# TestPoints.net
KiCad netlist of a schematic drawn in Altium Designer
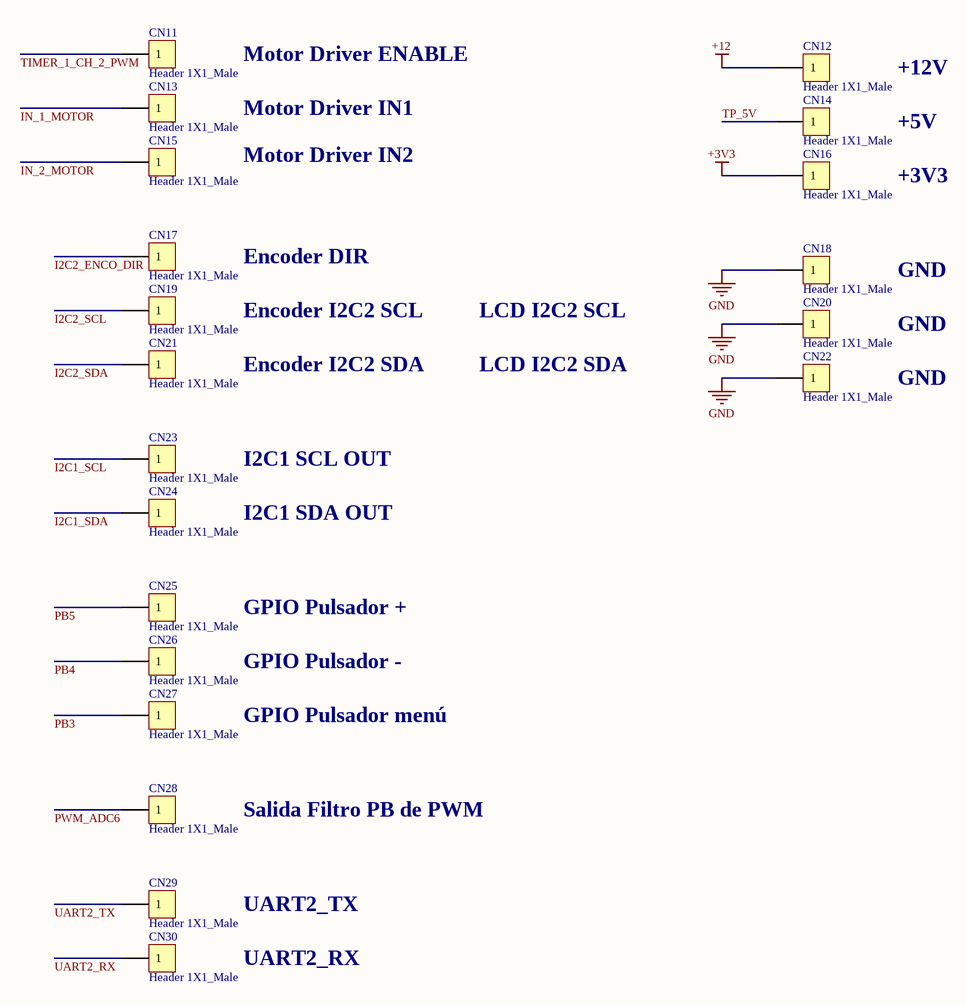
[diagram p0: TestPoints.SchDoc]

(export (version "E")
  (design (tool "Eeschema 10.0.6"))
  (components
    (comp (ref "CN11")
      (value "Header 1X1_Male")
      (footprint "1*1P_MALE")
      (description "Header, 1-Pin, Single row,male")
      (fields (field (name "PUBLISHER") "Altium Limited"))
      (libsource (lib "ProyectoTD3") (part "Header 1X1_Male"))
    )
    (comp (ref "CN12")
      (value "Header 1X1_Male")
      (footprint "1*1P_MALE")
      (description "Header, 1-Pin, Single row,male")
      (fields (field (name "PUBLISHER") "Altium Limited"))
      (libsource (lib "ProyectoTD3") (part "Header 1X1_Male"))
    )
    (comp (ref "CN13")
      (value "Header 1X1_Male")
      (footprint "1*1P_MALE")
      (description "Header, 1-Pin, Single row,male")
      (fields (field (name "PUBLISHER") "Altium Limited"))
      (libsource (lib "ProyectoTD3") (part "Header 1X1_Male"))
    )
    (comp (ref "CN14")
      (value "Header 1X1_Male")
      (footprint "1*1P_MALE")
      (description "Header, 1-Pin, Single row,male")
      (fields (field (name "PUBLISHER") "Altium Limited"))
      (libsource (lib "ProyectoTD3") (part "Header 1X1_Male"))
    )
    (comp (ref "CN15")
      (value "Header 1X1_Male")
      (footprint "1*1P_MALE")
      (description "Header, 1-Pin, Single row,male")
      (fields (field (name "PUBLISHER") "Altium Limited"))
      (libsource (lib "ProyectoTD3") (part "Header 1X1_Male"))
    )
    (comp (ref "CN16")
      (value "Header 1X1_Male")
      (footprint "1*1P_MALE")
      (description "Header, 1-Pin, Single row,male")
      (fields (field (name "PUBLISHER") "Altium Limited"))
      (libsource (lib "ProyectoTD3") (part "Header 1X1_Male"))
    )
    (comp (ref "CN17")
      (value "Header 1X1_Male")
      (footprint "1*1P_MALE")
      (description "Header, 1-Pin, Single row,male")
      (fields (field (name "PUBLISHER") "Altium Limited"))
      (libsource (lib "ProyectoTD3") (part "Header 1X1_Male"))
    )
    (comp (ref "CN18")
      (value "Header 1X1_Male")
      (footprint "1*1P_MALE")
      (description "Header, 1-Pin, Single row,male")
      (fields (field (name "PUBLISHER") "Altium Limited"))
      (libsource (lib "ProyectoTD3") (part "Header 1X1_Male"))
    )
    (comp (ref "CN19")
      (value "Header 1X1_Male")
      (footprint "1*1P_MALE")
      (description "Header, 1-Pin, Single row,male")
      (fields (field (name "PUBLISHER") "Altium Limited"))
      (libsource (lib "ProyectoTD3") (part "Header 1X1_Male"))
    )
    (comp (ref "CN20")
      (value "Header 1X1_Male")
      (footprint "1*1P_MALE")
      (description "Header, 1-Pin, Single row,male")
      (fields (field (name "PUBLISHER") "Altium Limited"))
      (libsource (lib "ProyectoTD3") (part "Header 1X1_Male"))
    )
    (comp (ref "CN21")
      (value "Header 1X1_Male")
      (footprint "1*1P_MALE")
      (description "Header, 1-Pin, Single row,male")
      (fields (field (name "PUBLISHER") "Altium Limited"))
      (libsource (lib "ProyectoTD3") (part "Header 1X1_Male"))
    )
    (comp (ref "CN22")
      (value "Header 1X1_Male")
      (footprint "1*1P_MALE")
      (description "Header, 1-Pin, Single row,male")
      (fields (field (name "PUBLISHER") "Altium Limited"))
      (libsource (lib "ProyectoTD3") (part "Header 1X1_Male"))
    )
    (comp (ref "CN23")
      (value "Header 1X1_Male")
      (footprint "1*1P_MALE")
      (description "Header, 1-Pin, Single row,male")
      (fields (field (name "PUBLISHER") "Altium Limited"))
      (libsource (lib "ProyectoTD3") (part "Header 1X1_Male"))
    )
    (comp (ref "CN24")
      (value "Header 1X1_Male")
      (footprint "1*1P_MALE")
      (description "Header, 1-Pin, Single row,male")
      (fields (field (name "PUBLISHER") "Altium Limited"))
      (libsource (lib "ProyectoTD3") (part "Header 1X1_Male"))
    )
    (comp (ref "CN25")
      (value "Header 1X1_Male")
      (footprint "1*1P_MALE")
      (description "Header, 1-Pin, Single row,male")
      (fields (field (name "PUBLISHER") "Altium Limited"))
      (libsource (lib "ProyectoTD3") (part "Header 1X1_Male"))
    )
    (comp (ref "CN26")
      (value "Header 1X1_Male")
      (footprint "1*1P_MALE")
      (description "Header, 1-Pin, Single row,male")
      (fields (field (name "PUBLISHER") "Altium Limited"))
      (libsource (lib "ProyectoTD3") (part "Header 1X1_Male"))
    )
    (comp (ref "CN27")
      (value "Header 1X1_Male")
      (footprint "1*1P_MALE")
      (description "Header, 1-Pin, Single row,male")
      (fields (field (name "PUBLISHER") "Altium Limited"))
      (libsource (lib "ProyectoTD3") (part "Header 1X1_Male"))
    )
    (comp (ref "CN28")
      (value "Header 1X1_Male")
      (footprint "1*1P_MALE")
      (description "Header, 1-Pin, Single row,male")
      (fields (field (name "PUBLISHER") "Altium Limited"))
      (libsource (lib "ProyectoTD3") (part "Header 1X1_Male"))
    )
    (comp (ref "CN29")
      (value "Header 1X1_Male")
      (footprint "1*1P_MALE")
      (description "Header, 1-Pin, Single row,male")
      (fields (field (name "PUBLISHER") "Altium Limited"))
      (libsource (lib "ProyectoTD3") (part "Header 1X1_Male"))
    )
    (comp (ref "CN30")
      (value "Header 1X1_Male")
      (footprint "1*1P_MALE")
      (description "Header, 1-Pin, Single row,male")
      (fields (field (name "PUBLISHER") "Altium Limited"))
      (libsource (lib "ProyectoTD3") (part "Header 1X1_Male"))
    )
  )
  (nets
    (net (code "1") (name "+3V3") (class "Default")
      (node (ref "CN16") (pin "1") (pinfunction "1_1") (pintype "passive"))
    )
    (net (code "2") (name "+12") (class "Default")
      (node (ref "CN12") (pin "1") (pinfunction "1_1") (pintype "passive"))
    )
    (net (code "3") (name "/I2C1_SCL") (class "Default")
      (node (ref "CN23") (pin "1") (pinfunction "1_1") (pintype "passive"))
    )
    (net (code "4") (name "/I2C1_SDA") (class "Default")
      (node (ref "CN24") (pin "1") (pinfunction "1_1") (pintype "passive"))
    )
    (net (code "5") (name "/I2C2_ENCO_DIR") (class "Default")
      (node (ref "CN17") (pin "1") (pinfunction "1_1") (pintype "passive"))
    )
    (net (code "6") (name "/I2C2_SCL") (class "Default")
      (node (ref "CN19") (pin "1") (pinfunction "1_1") (pintype "passive"))
    )
    (net (code "7") (name "/I2C2_SDA") (class "Default")
      (node (ref "CN21") (pin "1") (pinfunction "1_1") (pintype "passive"))
    )
    (net (code "8") (name "/IN_1_MOTOR") (class "Default")
      (node (ref "CN13") (pin "1") (pinfunction "1_1") (pintype "passive"))
    )
    (net (code "9") (name "/IN_2_MOTOR") (class "Default")
      (node (ref "CN15") (pin "1") (pinfunction "1_1") (pintype "passive"))
    )
    (net (code "10") (name "/PB3") (class "Default")
      (node (ref "CN27") (pin "1") (pinfunction "1_1") (pintype "passive"))
    )
    (net (code "11") (name "/PB4") (class "Default")
      (node (ref "CN26") (pin "1") (pinfunction "1_1") (pintype "passive"))
    )
    (net (code "12") (name "/PB5") (class "Default")
      (node (ref "CN25") (pin "1") (pinfunction "1_1") (pintype "passive"))
    )
    (net (code "13") (name "/PWM_ADC6") (class "Default")
      (node (ref "CN28") (pin "1") (pinfunction "1_1") (pintype "passive"))
    )
    (net (code "14") (name "/TIMER_1_CH_2_PWM") (class "Default")
      (node (ref "CN11") (pin "1") (pinfunction "1_1") (pintype "passive"))
    )
    (net (code "15") (name "/TP_5V") (class "Default")
      (node (ref "CN14") (pin "1") (pinfunction "1_1") (pintype "passive"))
    )
    (net (code "16") (name "/UART2_RX") (class "Default")
      (node (ref "CN30") (pin "1") (pinfunction "1_1") (pintype "passive"))
    )
    (net (code "17") (name "/UART2_TX") (class "Default")
      (node (ref "CN29") (pin "1") (pinfunction "1_1") (pintype "passive"))
    )
    (net (code "18") (name "GND") (class "Default")
      (node (ref "CN18") (pin "1") (pinfunction "1_1") (pintype "passive"))
      (node (ref "CN20") (pin "1") (pinfunction "1_1") (pintype "passive"))
      (node (ref "CN22") (pin "1") (pinfunction "1_1") (pintype "passive"))
    )
  )
)
